# OSO-MISC-20-016_Blinky_Board_for_Ring.net
KiCad netlist of a schematic drawn in EAGLE
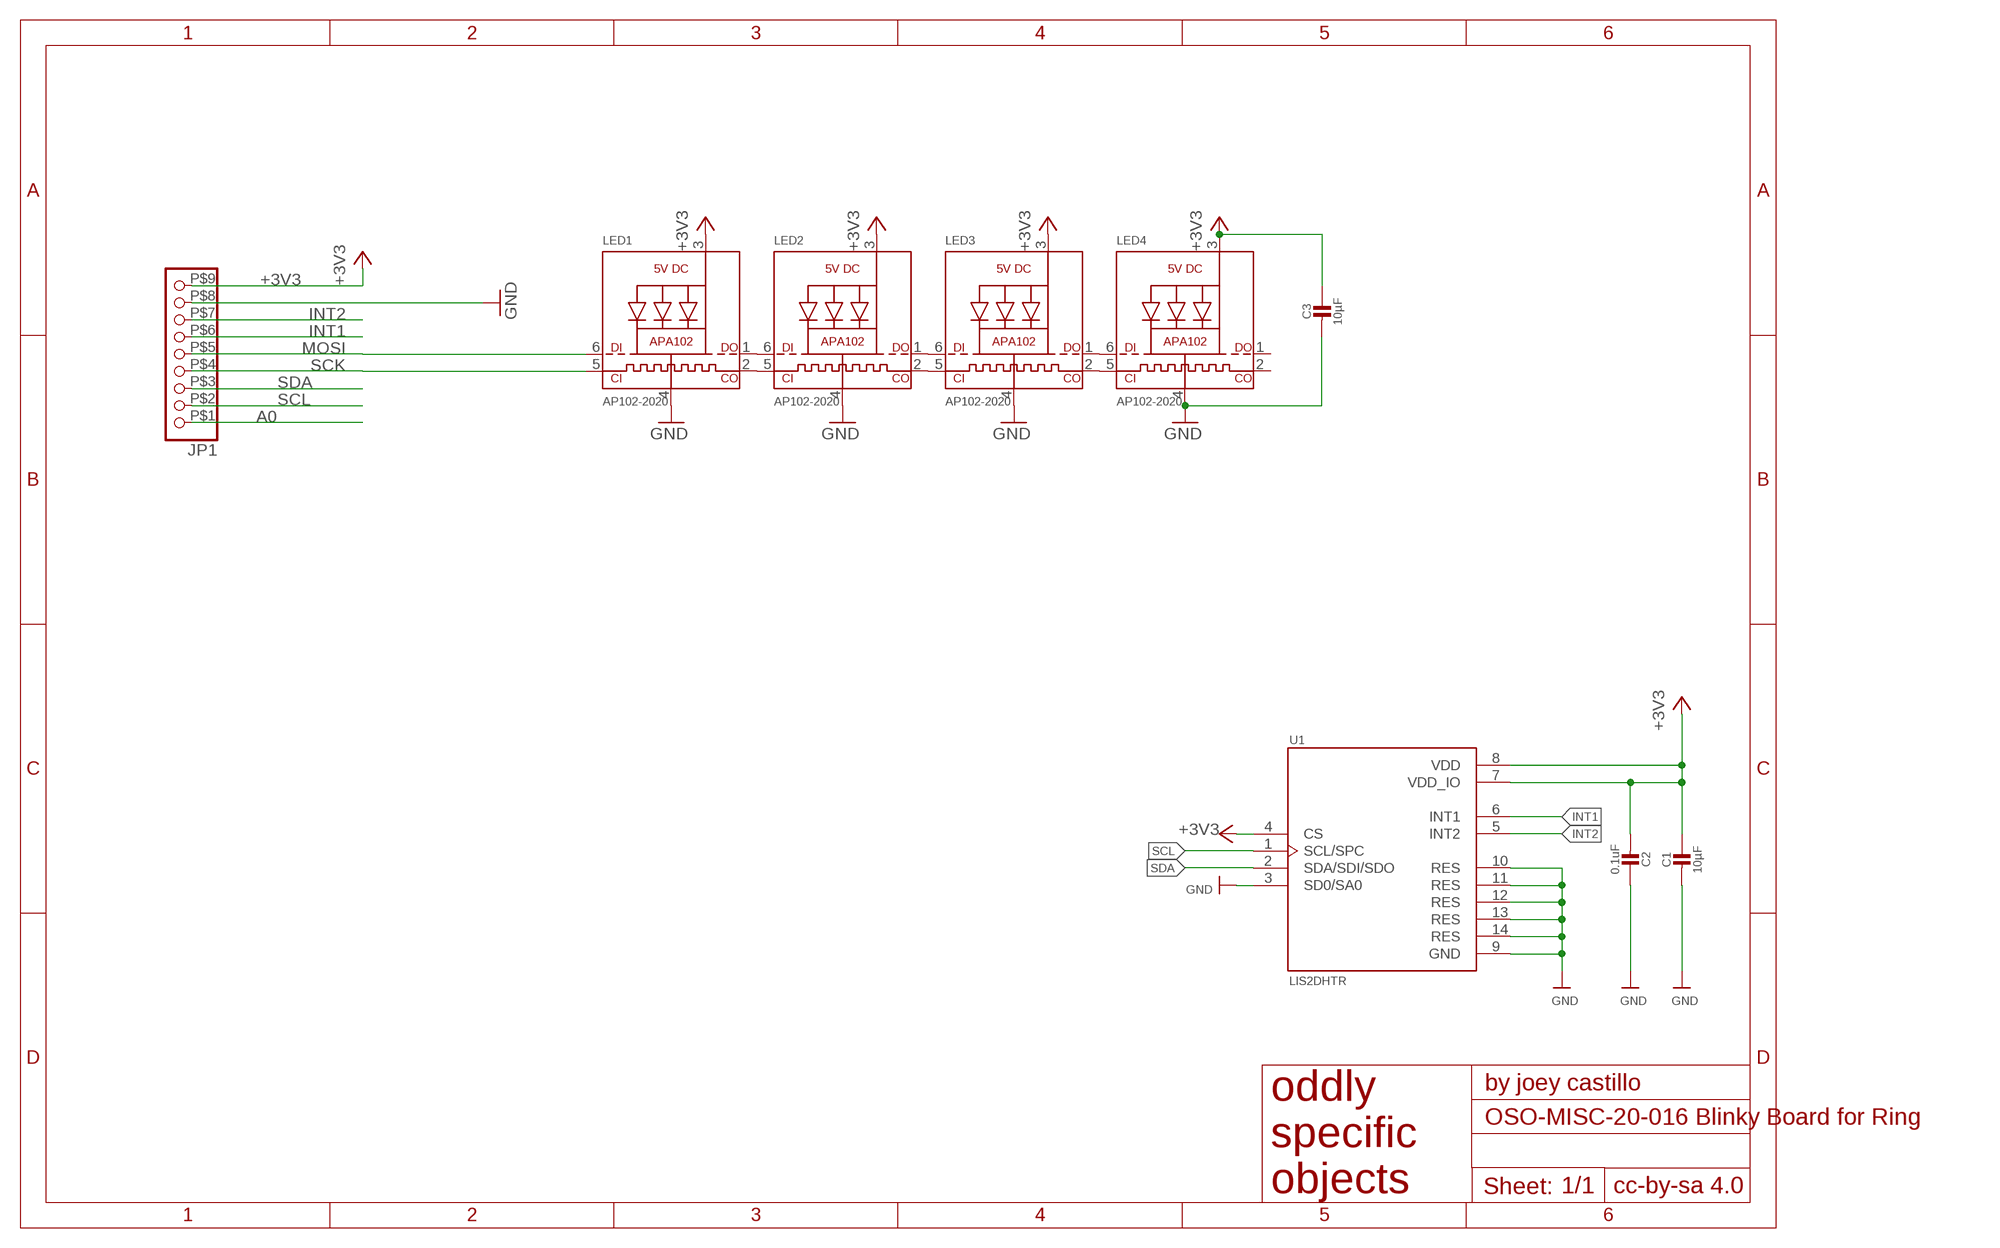
[diagram p0: schematic, sheet 1]

(export (version "E")
  (design (tool "Eeschema 10.0.6"))
  (components
    (comp (ref "C1")
      (value "10µF")
      (footprint "eagle-import:0805-NO")
      (libsource (lib "eagle-import") (part "CAP_CERAMIC0805-NOOUTLINE"))
    )
    (comp (ref "C2")
      (value "0.1uF")
      (footprint "eagle-import:0805-NO")
      (libsource (lib "eagle-import") (part "CAP_CERAMIC0805-NOOUTLINE"))
    )
    (comp (ref "C3")
      (value "10µF")
      (footprint "eagle-import:0805-NO")
      (libsource (lib "eagle-import") (part "CAP_CERAMIC0805-NOOUTLINE"))
    )
    (comp (ref "JP1")
      (value "HEADER-1X9BOARD_TO_FLEX")
      (footprint "eagle-import:9PIN_SMT_CONNECTOR")
      (libsource (lib "eagle-import") (part "HEADER-1X9BOARD_TO_FLEX"))
    )
    (comp (ref "LED1")
      (value "AP102-2020")
      (footprint "eagle-import:APA102_2020")
      (libsource (lib "eagle-import") (part "APA1022020"))
    )
    (comp (ref "LED2")
      (value "AP102-2020")
      (footprint "eagle-import:APA102_2020")
      (libsource (lib "eagle-import") (part "APA1022020"))
    )
    (comp (ref "LED3")
      (value "AP102-2020")
      (footprint "eagle-import:APA102_2020")
      (libsource (lib "eagle-import") (part "APA1022020"))
    )
    (comp (ref "LED4")
      (value "AP102-2020")
      (footprint "eagle-import:APA102_2020")
      (libsource (lib "eagle-import") (part "APA1022020"))
    )
    (comp (ref "U1")
      (value "LIS2DHTR")
      (footprint "eagle-import:PQFN35P200X200X100-14N")
      (fields (field (name "DIGI-KEY_PART_NUMBER") "497-13795-1-ND") (field (name "MF") "STMicroelectronics"))
      (libsource (lib "eagle-import") (part "LIS2DHTR"))
    )
  )
  (nets
    (net (code "1") (name "+3V3") (class "Default")
      (node (ref "C1") (pin "1") (pinfunction "1_1") (pintype "passive"))
      (node (ref "C2") (pin "2") (pinfunction "2_2") (pintype "passive"))
      (node (ref "C3") (pin "1") (pinfunction "1_1") (pintype "passive"))
      (node (ref "JP1") (pin "P$9") (pinfunction "9_P$9") (pintype "passive"))
      (node (ref "LED1") (pin "3") (pinfunction "VDD_3") (pintype "power_in"))
      (node (ref "LED2") (pin "3") (pinfunction "VDD_3") (pintype "power_in"))
      (node (ref "LED3") (pin "3") (pinfunction "VDD_3") (pintype "power_in"))
      (node (ref "LED4") (pin "3") (pinfunction "VDD_3") (pintype "power_in"))
      (node (ref "U1") (pin "4") (pinfunction "CS_4") (pintype "input"))
      (node (ref "U1") (pin "7") (pinfunction "VDD_IO_7") (pintype "power_in"))
      (node (ref "U1") (pin "8") (pinfunction "VDD_8") (pintype "power_in"))
    )
    (net (code "2") (name "/A0") (class "Default")
      (node (ref "JP1") (pin "P$1") (pinfunction "1_P$1") (pintype "passive"))
    )
    (net (code "3") (name "/MOSI") (class "Default")
      (node (ref "JP1") (pin "P$5") (pinfunction "5_P$5") (pintype "passive"))
      (node (ref "LED1") (pin "6") (pinfunction "DI_6") (pintype "input"))
    )
    (net (code "4") (name "/SCK") (class "Default")
      (node (ref "JP1") (pin "P$4") (pinfunction "4_P$4") (pintype "passive"))
      (node (ref "LED1") (pin "5") (pinfunction "CKI_5") (pintype "input"))
    )
    (net (code "5") (name "GND") (class "Default")
      (node (ref "C1") (pin "2") (pinfunction "2_2") (pintype "passive"))
      (node (ref "C2") (pin "1") (pinfunction "1_1") (pintype "passive"))
      (node (ref "C3") (pin "2") (pinfunction "2_2") (pintype "passive"))
      (node (ref "JP1") (pin "P$8") (pinfunction "8_P$8") (pintype "passive"))
      (node (ref "LED1") (pin "4") (pinfunction "GND_4") (pintype "power_in"))
      (node (ref "LED2") (pin "4") (pinfunction "GND_4") (pintype "power_in"))
      (node (ref "LED3") (pin "4") (pinfunction "GND_4") (pintype "power_in"))
      (node (ref "LED4") (pin "4") (pinfunction "GND_4") (pintype "power_in"))
      (node (ref "U1") (pin "10") (pinfunction "RES_10") (pintype "power_in"))
      (node (ref "U1") (pin "11") (pinfunction "RES_11") (pintype "power_in"))
      (node (ref "U1") (pin "12") (pinfunction "RES_12") (pintype "power_in"))
      (node (ref "U1") (pin "13") (pinfunction "RES_13") (pintype "power_in"))
      (node (ref "U1") (pin "14") (pinfunction "RES_14") (pintype "power_in"))
      (node (ref "U1") (pin "3") (pinfunction "SD0/SA0_3") (pintype "output"))
      (node (ref "U1") (pin "9") (pinfunction "GND_9") (pintype "power_in"))
    )
    (net (code "6") (name "INT1") (class "Default")
      (node (ref "JP1") (pin "P$6") (pinfunction "6_P$6") (pintype "passive"))
      (node (ref "U1") (pin "6") (pinfunction "INT1_6") (pintype "output"))
    )
    (net (code "7") (name "INT2") (class "Default")
      (node (ref "JP1") (pin "P$7") (pinfunction "7_P$7") (pintype "passive"))
      (node (ref "U1") (pin "5") (pinfunction "INT2_5") (pintype "output"))
    )
    (net (code "8") (name "Net-(LED1-CKO)") (class "Default")
      (node (ref "LED1") (pin "2") (pinfunction "CKO_2") (pintype "output"))
      (node (ref "LED2") (pin "5") (pinfunction "CKI_5") (pintype "input"))
    )
    (net (code "9") (name "Net-(LED1-DO)") (class "Default")
      (node (ref "LED1") (pin "1") (pinfunction "DO_1") (pintype "output"))
      (node (ref "LED2") (pin "6") (pinfunction "DI_6") (pintype "input"))
    )
    (net (code "10") (name "Net-(LED2-CKO)") (class "Default")
      (node (ref "LED2") (pin "2") (pinfunction "CKO_2") (pintype "output"))
      (node (ref "LED3") (pin "5") (pinfunction "CKI_5") (pintype "input"))
    )
    (net (code "11") (name "Net-(LED2-DO)") (class "Default")
      (node (ref "LED2") (pin "1") (pinfunction "DO_1") (pintype "output"))
      (node (ref "LED3") (pin "6") (pinfunction "DI_6") (pintype "input"))
    )
    (net (code "12") (name "Net-(LED3-CKO)") (class "Default")
      (node (ref "LED3") (pin "2") (pinfunction "CKO_2") (pintype "output"))
      (node (ref "LED4") (pin "5") (pinfunction "CKI_5") (pintype "input"))
    )
    (net (code "13") (name "Net-(LED3-DO)") (class "Default")
      (node (ref "LED3") (pin "1") (pinfunction "DO_1") (pintype "output"))
      (node (ref "LED4") (pin "6") (pinfunction "DI_6") (pintype "input"))
    )
    (net (code "14") (name "SCL") (class "Default")
      (node (ref "JP1") (pin "P$2") (pinfunction "2_P$2") (pintype "passive"))
      (node (ref "U1") (pin "1") (pinfunction "SCL/SPC_1") (pintype "input"))
    )
    (net (code "15") (name "SDA") (class "Default")
      (node (ref "JP1") (pin "P$3") (pinfunction "3_P$3") (pintype "passive"))
      (node (ref "U1") (pin "2") (pinfunction "SDA/SDI/SDO_2") (pintype "bidirectional"))
    )
    (net (code "16") (name "unconnected-(LED4-CKO-Pad2)") (class "Default")
      (node (ref "LED4") (pin "2") (pinfunction "CKO_2") (pintype "output"))
    )
    (net (code "17") (name "unconnected-(LED4-DO-Pad1)") (class "Default")
      (node (ref "LED4") (pin "1") (pinfunction "DO_1") (pintype "output"))
    )
  )
)
